# Mini_Sumo.net
KiCad netlist of a schematic drawn in EAGLE
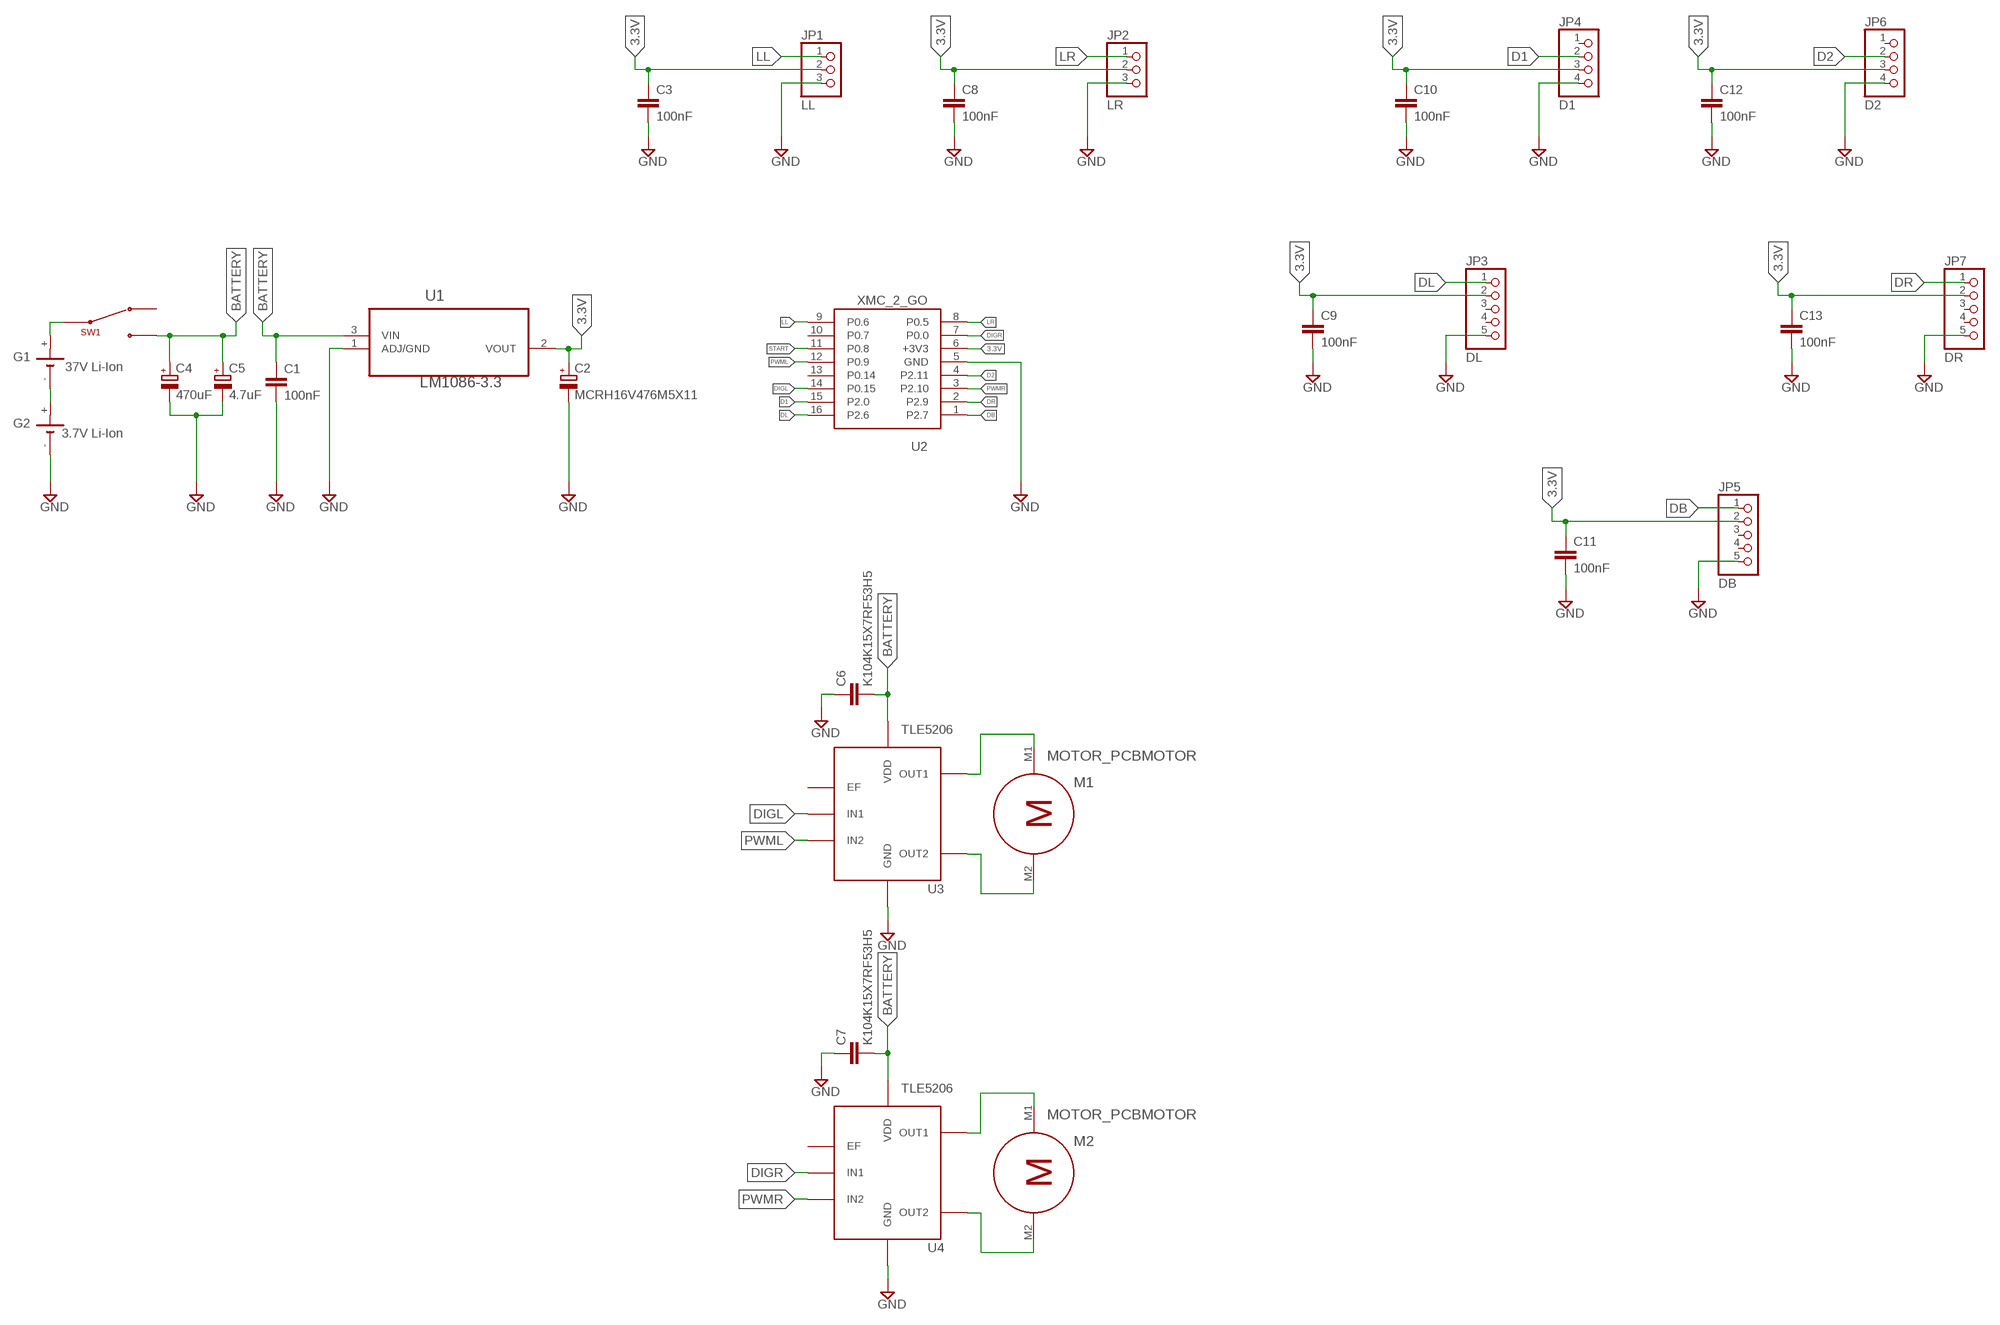
[diagram p0: schematic, sheet 1]

(export (version "E")
  (design (tool "Eeschema 10.0.6"))
  (components
    (comp (ref "C1")
      (value "100nF")
      (footprint "eagle-import:C025-025X050")
      (libsource (lib "eagle-import") (part "C-EU025-025X050"))
    )
    (comp (ref "C2")
      (value "MCRH16V476M5X11")
      (footprint "eagle-import:E2,5-5")
      (libsource (lib "eagle-import") (part "CPOL-EUE2.5-5"))
    )
    (comp (ref "C3")
      (value "100nF")
      (footprint "eagle-import:C025-025X050")
      (libsource (lib "eagle-import") (part "C-EU025-025X050"))
    )
    (comp (ref "C4")
      (value "470uF")
      (footprint "eagle-import:E2,5-5")
      (libsource (lib "eagle-import") (part "CPOL-EUE2.5-5"))
    )
    (comp (ref "C5")
      (value "4.7uF")
      (footprint "eagle-import:E2,5-5")
      (libsource (lib "eagle-import") (part "CPOL-EUE2.5-5"))
    )
    (comp (ref "C6")
      (value "K104K15X7RF53H5")
      (footprint "eagle-import:C025-025X050")
      (libsource (lib "eagle-import") (part "C-EU025-025X050"))
    )
    (comp (ref "C7")
      (value "K104K15X7RF53H5")
      (footprint "eagle-import:C025-025X050")
      (libsource (lib "eagle-import") (part "C-EU025-025X050"))
    )
    (comp (ref "C8")
      (value "100nF")
      (footprint "eagle-import:C025-025X050")
      (libsource (lib "eagle-import") (part "C-EU025-025X050"))
    )
    (comp (ref "C9")
      (value "100nF")
      (footprint "eagle-import:C025-025X050")
      (libsource (lib "eagle-import") (part "C-EU025-025X050"))
    )
    (comp (ref "C10")
      (value "100nF")
      (footprint "eagle-import:C025-025X050")
      (libsource (lib "eagle-import") (part "C-EU025-025X050"))
    )
    (comp (ref "C11")
      (value "100nF")
      (footprint "eagle-import:C025-025X050")
      (libsource (lib "eagle-import") (part "C-EU025-025X050"))
    )
    (comp (ref "C12")
      (value "100nF")
      (footprint "eagle-import:C025-025X050")
      (libsource (lib "eagle-import") (part "C-EU025-025X050"))
    )
    (comp (ref "C13")
      (value "100nF")
      (footprint "eagle-import:C025-025X050")
      (libsource (lib "eagle-import") (part "C-EU025-025X050"))
    )
    (comp (ref "G1")
      (value "37V Li-Ion")
      (footprint "eagle-import:CH291-1220LF")
      (libsource (lib "eagle-import") (part "CH291-1220LF"))
    )
    (comp (ref "G2")
      (value "3.7V Li-Ion")
      (footprint "eagle-import:CH291-1220LF")
      (libsource (lib "eagle-import") (part "CH291-1220LF"))
    )
    (comp (ref "JP1")
      (value "LL")
      (footprint "eagle-import:1X03")
      (libsource (lib "eagle-import") (part "PINHD-1X3"))
    )
    (comp (ref "JP2")
      (value "LR")
      (footprint "eagle-import:1X03")
      (libsource (lib "eagle-import") (part "PINHD-1X3"))
    )
    (comp (ref "JP3")
      (value "DL")
      (footprint "eagle-import:1X05")
      (libsource (lib "eagle-import") (part "PINHD-1X5"))
    )
    (comp (ref "JP4")
      (value "D1")
      (footprint "eagle-import:1X04")
      (libsource (lib "eagle-import") (part "PINHD-1X4"))
    )
    (comp (ref "JP5")
      (value "DB")
      (footprint "eagle-import:1X05")
      (libsource (lib "eagle-import") (part "PINHD-1X5"))
    )
    (comp (ref "JP6")
      (value "D2")
      (footprint "eagle-import:1X04")
      (libsource (lib "eagle-import") (part "PINHD-1X4"))
    )
    (comp (ref "JP7")
      (value "DR")
      (footprint "eagle-import:1X05")
      (libsource (lib "eagle-import") (part "PINHD-1X5"))
    )
    (comp (ref "M1")
      (value "MOTOR_PCBMOTOR")
      (footprint "eagle-import:MICRO-MOTOR")
      (libsource (lib "eagle-import") (part "MOTOR_PCBMOTOR"))
    )
    (comp (ref "M2")
      (value "MOTOR_PCBMOTOR")
      (footprint "eagle-import:MICRO-MOTOR")
      (libsource (lib "eagle-import") (part "MOTOR_PCBMOTOR"))
    )
    (comp (ref "SW1")
      (value "SWITCH1OFF2")
      (footprint "eagle-import:MS111")
      (libsource (lib "eagle-import") (part "SWITCH1OFF2"))
    )
    (comp (ref "U1")
      (value "LM1086-3.3")
      (footprint "eagle-import:TO254P470X1016X2222-3P")
      (fields (field (name "MPN") "LM1086CT-5.0"))
      (libsource (lib "eagle-import") (part "LM1086CT-5.0"))
    )
    (comp (ref "U2")
      (value "XMC_2_GO")
      (footprint "eagle-import:XMC_2_GO")
      (libsource (lib "eagle-import") (part "XMC_2_GO"))
    )
    (comp (ref "U3")
      (value "TLE5206")
      (footprint "eagle-import:INF-PG-TO263-7-1_L_1PRIMARY")
      (libsource (lib "eagle-import") (part "TLE5206"))
    )
    (comp (ref "U4")
      (value "TLE5206")
      (footprint "eagle-import:INF-PG-TO263-7-1_L_1PRIMARY")
      (libsource (lib "eagle-import") (part "TLE5206"))
    )
  )
  (nets
    (net (code "1") (name "3.3V") (class "Default")
      (node (ref "C10") (pin "1") (pinfunction "1_1") (pintype "passive"))
      (node (ref "C11") (pin "1") (pinfunction "1_1") (pintype "passive"))
      (node (ref "C12") (pin "1") (pinfunction "1_1") (pintype "passive"))
      (node (ref "C13") (pin "1") (pinfunction "1_1") (pintype "passive"))
      (node (ref "C2") (pin "+") (pinfunction "+_+") (pintype "passive"))
      (node (ref "C3") (pin "1") (pinfunction "1_1") (pintype "passive"))
      (node (ref "C8") (pin "1") (pinfunction "1_1") (pintype "passive"))
      (node (ref "C9") (pin "1") (pinfunction "1_1") (pintype "passive"))
      (node (ref "JP1") (pin "2") (pinfunction "2_2") (pintype "passive"))
      (node (ref "JP2") (pin "2") (pinfunction "2_2") (pintype "passive"))
      (node (ref "JP3") (pin "2") (pinfunction "2_2") (pintype "passive"))
      (node (ref "JP4") (pin "3") (pinfunction "3_3") (pintype "passive"))
      (node (ref "JP5") (pin "2") (pinfunction "2_2") (pintype "passive"))
      (node (ref "JP6") (pin "3") (pinfunction "3_3") (pintype "passive"))
      (node (ref "JP7") (pin "2") (pinfunction "2_2") (pintype "passive"))
      (node (ref "U1") (pin "2") (pinfunction "VOUT_2") (pintype "output"))
      (node (ref "U2") (pin "6") (pinfunction "+3V3_6") (pintype "bidirectional"))
    )
    (net (code "2") (name "BATTERY") (class "Default")
      (node (ref "C1") (pin "1") (pinfunction "1_1") (pintype "passive"))
      (node (ref "C4") (pin "+") (pinfunction "+_+") (pintype "passive"))
      (node (ref "C5") (pin "+") (pinfunction "+_+") (pintype "passive"))
      (node (ref "C6") (pin "2") (pinfunction "2_2") (pintype "passive"))
      (node (ref "C7") (pin "2") (pinfunction "2_2") (pintype "passive"))
      (node (ref "SW1") (pin "P$3") (pinfunction "2_P$3") (pintype "bidirectional"))
      (node (ref "U1") (pin "3") (pinfunction "VIN_3") (pintype "input"))
      (node (ref "U3") (pin "6") (pinfunction "VDD_6") (pintype "power_in"))
      (node (ref "U4") (pin "6") (pinfunction "VDD_6") (pintype "power_in"))
    )
    (net (code "3") (name "D1") (class "Default")
      (node (ref "JP4") (pin "2") (pinfunction "2_2") (pintype "passive"))
      (node (ref "U2") (pin "15") (pinfunction "P2.0_15") (pintype "bidirectional"))
    )
    (net (code "4") (name "D2") (class "Default")
      (node (ref "JP6") (pin "2") (pinfunction "2_2") (pintype "passive"))
      (node (ref "U2") (pin "4") (pinfunction "P2.11_4") (pintype "bidirectional"))
    )
    (net (code "5") (name "DB") (class "Default")
      (node (ref "JP5") (pin "1") (pinfunction "1_1") (pintype "passive"))
      (node (ref "U2") (pin "1") (pinfunction "P2.7_1") (pintype "bidirectional"))
    )
    (net (code "6") (name "DIGL") (class "Default")
      (node (ref "U2") (pin "14") (pinfunction "P0.15_14") (pintype "bidirectional"))
      (node (ref "U3") (pin "3") (pinfunction "IN1_3") (pintype "input"))
    )
    (net (code "7") (name "DIGR") (class "Default")
      (node (ref "U2") (pin "7") (pinfunction "P0.0_7") (pintype "bidirectional"))
      (node (ref "U4") (pin "3") (pinfunction "IN1_3") (pintype "input"))
    )
    (net (code "8") (name "DL") (class "Default")
      (node (ref "JP3") (pin "1") (pinfunction "1_1") (pintype "passive"))
      (node (ref "U2") (pin "16") (pinfunction "P2.6_16") (pintype "bidirectional"))
    )
    (net (code "9") (name "DR") (class "Default")
      (node (ref "JP7") (pin "1") (pinfunction "1_1") (pintype "passive"))
      (node (ref "U2") (pin "2") (pinfunction "P2.9_2") (pintype "bidirectional"))
    )
    (net (code "10") (name "GND") (class "Default")
      (node (ref "C1") (pin "2") (pinfunction "2_2") (pintype "passive"))
      (node (ref "C10") (pin "2") (pinfunction "2_2") (pintype "passive"))
      (node (ref "C11") (pin "2") (pinfunction "2_2") (pintype "passive"))
      (node (ref "C12") (pin "2") (pinfunction "2_2") (pintype "passive"))
      (node (ref "C13") (pin "2") (pinfunction "2_2") (pintype "passive"))
      (node (ref "C2") (pin "-") (pinfunction "-_-") (pintype "passive"))
      (node (ref "C3") (pin "2") (pinfunction "2_2") (pintype "passive"))
      (node (ref "C4") (pin "-") (pinfunction "-_-") (pintype "passive"))
      (node (ref "C5") (pin "-") (pinfunction "-_-") (pintype "passive"))
      (node (ref "C6") (pin "1") (pinfunction "1_1") (pintype "passive"))
      (node (ref "C7") (pin "1") (pinfunction "1_1") (pintype "passive"))
      (node (ref "C8") (pin "2") (pinfunction "2_2") (pintype "passive"))
      (node (ref "C9") (pin "2") (pinfunction "2_2") (pintype "passive"))
      (node (ref "G2") (pin "-") (pinfunction "-_-") (pintype "passive"))
      (node (ref "JP1") (pin "3") (pinfunction "3_3") (pintype "passive"))
      (node (ref "JP2") (pin "3") (pinfunction "3_3") (pintype "passive"))
      (node (ref "JP3") (pin "5") (pinfunction "5_5") (pintype "passive"))
      (node (ref "JP4") (pin "4") (pinfunction "4_4") (pintype "passive"))
      (node (ref "JP5") (pin "5") (pinfunction "5_5") (pintype "passive"))
      (node (ref "JP6") (pin "4") (pinfunction "4_4") (pintype "passive"))
      (node (ref "JP7") (pin "5") (pinfunction "5_5") (pintype "passive"))
      (node (ref "U1") (pin "1") (pinfunction "ADJ/GND_1") (pintype "passive"))
      (node (ref "U2") (pin "5") (pinfunction "GND_5") (pintype "bidirectional"))
      (node (ref "U3") (pin "4") (pinfunction "GND_4") (pintype "power_in"))
      (node (ref "U3") (pin "8") (pinfunction "GND_8") (pintype "power_in"))
      (node (ref "U4") (pin "4") (pinfunction "GND_4") (pintype "power_in"))
      (node (ref "U4") (pin "8") (pinfunction "GND_8") (pintype "power_in"))
    )
    (net (code "11") (name "LL") (class "Default")
      (node (ref "JP1") (pin "1") (pinfunction "1_1") (pintype "passive"))
      (node (ref "U2") (pin "9") (pinfunction "P0.6_9") (pintype "bidirectional"))
    )
    (net (code "12") (name "LR") (class "Default")
      (node (ref "JP2") (pin "1") (pinfunction "1_1") (pintype "passive"))
      (node (ref "U2") (pin "8") (pinfunction "P0.5_8") (pintype "bidirectional"))
    )
    (net (code "13") (name "Net-(G1-Pad-)") (class "Default")
      (node (ref "G1") (pin "-") (pinfunction "-_-") (pintype "passive"))
      (node (ref "G2") (pin "+") (pinfunction "+_+") (pintype "passive"))
    )
    (net (code "14") (name "Net-(M1-1)") (class "Default")
      (node (ref "M1") (pin "M1") (pinfunction "1_M1") (pintype "bidirectional"))
      (node (ref "U3") (pin "1") (pinfunction "OUT1_1") (pintype "output"))
    )
    (net (code "15") (name "Net-(M1-2)") (class "Default")
      (node (ref "M1") (pin "M2") (pinfunction "2_M2") (pintype "bidirectional"))
      (node (ref "U3") (pin "7") (pinfunction "OUT2_7") (pintype "output"))
    )
    (net (code "16") (name "Net-(M2-1)") (class "Default")
      (node (ref "M2") (pin "M1") (pinfunction "1_M1") (pintype "bidirectional"))
      (node (ref "U4") (pin "1") (pinfunction "OUT1_1") (pintype "output"))
    )
    (net (code "17") (name "Net-(M2-2)") (class "Default")
      (node (ref "M2") (pin "M2") (pinfunction "2_M2") (pintype "bidirectional"))
      (node (ref "U4") (pin "7") (pinfunction "OUT2_7") (pintype "output"))
    )
    (net (code "18") (name "Net-(SW1-COM)") (class "Default")
      (node (ref "G1") (pin "+") (pinfunction "+_+") (pintype "passive"))
      (node (ref "SW1") (pin "P$2") (pinfunction "COM_P$2") (pintype "bidirectional"))
    )
    (net (code "19") (name "PWML") (class "Default")
      (node (ref "U2") (pin "12") (pinfunction "P0.9_12") (pintype "bidirectional"))
      (node (ref "U3") (pin "5") (pinfunction "IN2_5") (pintype "input"))
    )
    (net (code "20") (name "PWMR") (class "Default")
      (node (ref "U2") (pin "3") (pinfunction "P2.10_3") (pintype "bidirectional"))
      (node (ref "U4") (pin "5") (pinfunction "IN2_5") (pintype "input"))
    )
    (net (code "21") (name "START") (class "Default")
      (node (ref "U2") (pin "11") (pinfunction "P0.8_11") (pintype "bidirectional"))
    )
    (net (code "22") (name "unconnected-(JP3-Pad3)") (class "Default")
      (node (ref "JP3") (pin "3") (pinfunction "3_3") (pintype "passive"))
    )
    (net (code "23") (name "unconnected-(JP3-Pad4)") (class "Default")
      (node (ref "JP3") (pin "4") (pinfunction "4_4") (pintype "passive"))
    )
    (net (code "24") (name "unconnected-(JP4-Pad1)") (class "Default")
      (node (ref "JP4") (pin "1") (pinfunction "1_1") (pintype "passive"))
    )
    (net (code "25") (name "unconnected-(JP5-Pad3)") (class "Default")
      (node (ref "JP5") (pin "3") (pinfunction "3_3") (pintype "passive"))
    )
    (net (code "26") (name "unconnected-(JP5-Pad4)") (class "Default")
      (node (ref "JP5") (pin "4") (pinfunction "4_4") (pintype "passive"))
    )
    (net (code "27") (name "unconnected-(JP6-Pad1)") (class "Default")
      (node (ref "JP6") (pin "1") (pinfunction "1_1") (pintype "passive"))
    )
    (net (code "28") (name "unconnected-(JP7-Pad3)") (class "Default")
      (node (ref "JP7") (pin "3") (pinfunction "3_3") (pintype "passive"))
    )
    (net (code "29") (name "unconnected-(JP7-Pad4)") (class "Default")
      (node (ref "JP7") (pin "4") (pinfunction "4_4") (pintype "passive"))
    )
    (net (code "30") (name "unconnected-(SW1-1-PadP$1)") (class "Default")
      (node (ref "SW1") (pin "P$1") (pinfunction "1_P$1") (pintype "bidirectional"))
    )
    (net (code "31") (name "unconnected-(U2-P0.7-Pad10)") (class "Default")
      (node (ref "U2") (pin "10") (pinfunction "P0.7_10") (pintype "bidirectional"))
    )
    (net (code "32") (name "unconnected-(U2-P0.14-Pad13)") (class "Default")
      (node (ref "U2") (pin "13") (pinfunction "P0.14_13") (pintype "bidirectional"))
    )
    (net (code "33") (name "unconnected-(U3-EF-Pad2)") (class "Default")
      (node (ref "U3") (pin "2") (pinfunction "EF_2") (pintype "output"))
    )
    (net (code "34") (name "unconnected-(U4-EF-Pad2)") (class "Default")
      (node (ref "U4") (pin "2") (pinfunction "EF_2") (pintype "output"))
    )
  )
)
